# BT-USB.net
KiCad netlist of a schematic drawn in EAGLE
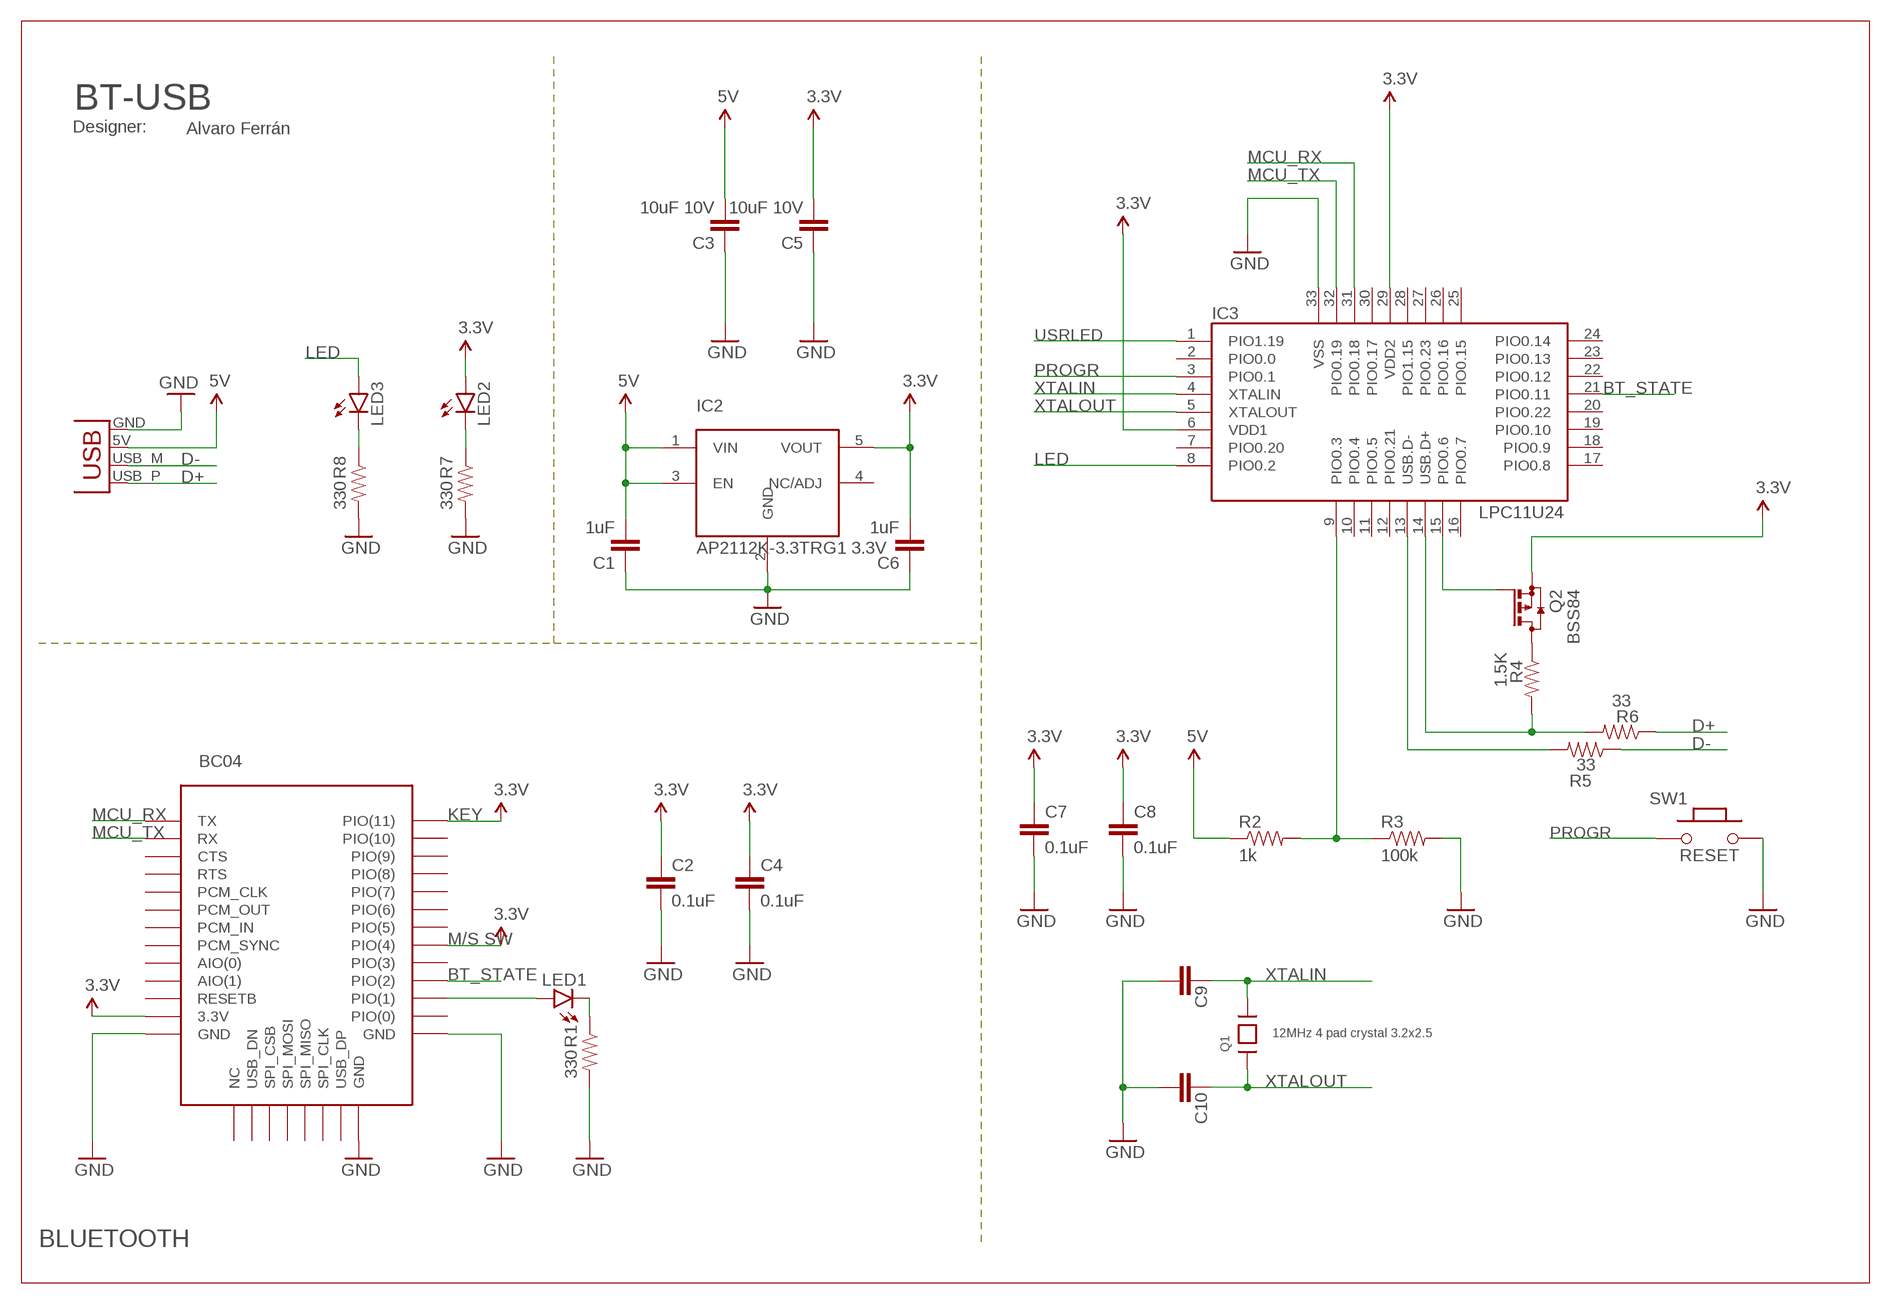
[diagram p0: schematic, sheet 1]

(export (version "E")
  (design (tool "Eeschema 10.0.6"))
  (components
    (comp (ref "C1")
      (value "1uF")
      (footprint "eagle-import:0402-CAP")
      (libsource (lib "eagle-import") (part "CAP0402-CAP"))
    )
    (comp (ref "C2")
      (value "0.1uF")
      (footprint "eagle-import:0402-CAP")
      (libsource (lib "eagle-import") (part "CAP0402-CAP"))
    )
    (comp (ref "C3")
      (value "10uF 10V")
      (footprint "eagle-import:0402-CAP")
      (libsource (lib "eagle-import") (part "CAP0402-CAP"))
    )
    (comp (ref "C4")
      (value "0.1uF")
      (footprint "eagle-import:0402-CAP")
      (libsource (lib "eagle-import") (part "CAP0402-CAP"))
    )
    (comp (ref "C5")
      (value "10uF 10V")
      (footprint "eagle-import:0402-CAP")
      (libsource (lib "eagle-import") (part "CAP0402-CAP"))
    )
    (comp (ref "C6")
      (value "1uF")
      (footprint "eagle-import:0402-CAP")
      (libsource (lib "eagle-import") (part "CAP0402-CAP"))
    )
    (comp (ref "C7")
      (value "0.1uF")
      (footprint "eagle-import:0402-CAP")
      (libsource (lib "eagle-import") (part "CAP0402-CAP"))
    )
    (comp (ref "C8")
      (value "0.1uF")
      (footprint "eagle-import:0402-CAP")
      (libsource (lib "eagle-import") (part "CAP0402-CAP"))
    )
    (comp (ref "C9")
      (value "27pF")
      (footprint "eagle-import:0402-CAP")
      (libsource (lib "eagle-import") (part "CAP0402-CAP"))
    )
    (comp (ref "C10")
      (value "27pF")
      (footprint "eagle-import:0402-CAP")
      (libsource (lib "eagle-import") (part "CAP0402-CAP"))
    )
    (comp (ref "IC1")
      (value "BC04_BLUETOOTH")
      (footprint "eagle-import:BC04")
      (libsource (lib "eagle-import") (part "BC04_BLUETOOTH"))
    )
    (comp (ref "IC2")
      (value "AP2112K-3.3TRG1 3.3V")
      (footprint "eagle-import:SOT23-5")
      (libsource (lib "eagle-import") (part "5PIN_REG"))
    )
    (comp (ref "IC3")
      (value "LPC11U24")
      (footprint "eagle-import:HVQFN33_5X5MM")
      (libsource (lib "eagle-import") (part "LPC11U2X_HVQFN33(5X5)"))
    )
    (comp (ref "J1")
      (value "USBPCB")
      (footprint "eagle-import:USB-A-PCB")
      (libsource (lib "eagle-import") (part "USBPCB"))
    )
    (comp (ref "LED1")
      (value "LED0603")
      (footprint "eagle-import:LED-0603")
      (libsource (lib "eagle-import") (part "LED0603"))
    )
    (comp (ref "LED2")
      (value "LED0603")
      (footprint "eagle-import:LED-0603")
      (libsource (lib "eagle-import") (part "LED0603"))
    )
    (comp (ref "LED3")
      (value "LED0603")
      (footprint "eagle-import:LED-0603")
      (libsource (lib "eagle-import") (part "LED0603"))
    )
    (comp (ref "Q1")
      (value "12MHz 4 pad crystal 3.2x2.5")
      (footprint "eagle-import:CRYSTAL_3.2X2.5")
      (libsource (lib "eagle-import") (part "CRYSTAL3.2X2.5"))
    )
    (comp (ref "Q2")
      (value "BSS84")
      (footprint "eagle-import:SOT23")
      (libsource (lib "eagle-import") (part "BSS84"))
    )
    (comp (ref "R1")
      (value "330")
      (footprint "eagle-import:0402-RES")
      (libsource (lib "eagle-import") (part "RESISTOR0402-RES"))
    )
    (comp (ref "R2")
      (value "1k")
      (footprint "eagle-import:0402-RES")
      (libsource (lib "eagle-import") (part "RESISTOR0402-RES"))
    )
    (comp (ref "R3")
      (value "100k")
      (footprint "eagle-import:0402-RES")
      (libsource (lib "eagle-import") (part "RESISTOR0402-RES"))
    )
    (comp (ref "R4")
      (value "1.5K")
      (footprint "eagle-import:0402-RES")
      (libsource (lib "eagle-import") (part "RESISTOR0402-RES"))
    )
    (comp (ref "R5")
      (value "33")
      (footprint "eagle-import:0402-RES")
      (libsource (lib "eagle-import") (part "RESISTOR0402-RES"))
    )
    (comp (ref "R6")
      (value "33")
      (footprint "eagle-import:0402-RES")
      (libsource (lib "eagle-import") (part "RESISTOR0402-RES"))
    )
    (comp (ref "R7")
      (value "330")
      (footprint "eagle-import:0402-RES")
      (libsource (lib "eagle-import") (part "RESISTOR0402-RES"))
    )
    (comp (ref "R8")
      (value "330")
      (footprint "eagle-import:0402-RES")
      (libsource (lib "eagle-import") (part "RESISTOR0402-RES"))
    )
    (comp (ref "SW1")
      (value "RESET")
      (footprint "eagle-import:157SW")
      (libsource (lib "eagle-import") (part "PB157"))
    )
  )
  (nets
    (net (code "1") (name "/BT_STATE") (class "Default")
      (node (ref "IC1") (pin "P$25") (pinfunction "PIO(2)_P$25") (pintype "bidirectional"))
      (node (ref "IC3") (pin "21") (pinfunction "PIO0.11_21") (pintype "bidirectional"))
    )
    (net (code "2") (name "/D+") (class "Default")
      (node (ref "J1") (pin "USB_P") (pinfunction "D+_USB_P") (pintype "bidirectional"))
      (node (ref "R6") (pin "1") (pinfunction "1_1") (pintype "passive"))
    )
    (net (code "3") (name "/D-") (class "Default")
      (node (ref "J1") (pin "USB_M") (pinfunction "D-_USB_M") (pintype "bidirectional"))
      (node (ref "R5") (pin "1") (pinfunction "1_1") (pintype "passive"))
    )
    (net (code "4") (name "/LED") (class "Default")
      (node (ref "IC3") (pin "8") (pinfunction "PIO0.2_8") (pintype "bidirectional"))
      (node (ref "LED3") (pin "A") (pinfunction "A_A") (pintype "passive"))
    )
    (net (code "5") (name "/MCU_RX") (class "Default")
      (node (ref "IC1") (pin "P$1") (pinfunction "TX_P$1") (pintype "bidirectional"))
      (node (ref "IC3") (pin "31") (pinfunction "PIO0.18_31") (pintype "bidirectional"))
    )
    (net (code "6") (name "/MCU_TX") (class "Default")
      (node (ref "IC1") (pin "P$2") (pinfunction "RX_P$2") (pintype "bidirectional"))
      (node (ref "IC3") (pin "32") (pinfunction "PIO0.19_32") (pintype "bidirectional"))
    )
    (net (code "7") (name "/PROGR") (class "Default")
      (node (ref "IC3") (pin "3") (pinfunction "PIO0.1_3") (pintype "bidirectional"))
      (node (ref "SW1") (pin "1") (pinfunction "1_1") (pintype "passive"))
    )
    (net (code "8") (name "/USRLED") (class "Default")
      (node (ref "IC3") (pin "1") (pinfunction "PIO1.19_1") (pintype "bidirectional"))
    )
    (net (code "9") (name "/XTALIN") (class "Default")
      (node (ref "C9") (pin "1") (pinfunction "1_1") (pintype "passive"))
      (node (ref "IC3") (pin "4") (pinfunction "XTALIN_4") (pintype "bidirectional"))
      (node (ref "Q1") (pin "3") (pinfunction "P$2_3") (pintype "passive"))
    )
    (net (code "10") (name "/XTALOUT") (class "Default")
      (node (ref "C10") (pin "1") (pinfunction "1_1") (pintype "passive"))
      (node (ref "IC3") (pin "5") (pinfunction "XTALOUT_5") (pintype "bidirectional"))
      (node (ref "Q1") (pin "1") (pinfunction "P$1_1") (pintype "passive"))
    )
    (net (code "11") (name "3.3V") (class "Default")
      (node (ref "C2") (pin "1") (pinfunction "1_1") (pintype "passive"))
      (node (ref "C4") (pin "1") (pinfunction "1_1") (pintype "passive"))
      (node (ref "C5") (pin "2") (pinfunction "2_2") (pintype "passive"))
      (node (ref "C6") (pin "2") (pinfunction "2_2") (pintype "passive"))
      (node (ref "C7") (pin "1") (pinfunction "1_1") (pintype "passive"))
      (node (ref "C8") (pin "1") (pinfunction "1_1") (pintype "passive"))
      (node (ref "IC1") (pin "P$12") (pinfunction "3.3V_P$12") (pintype "bidirectional"))
      (node (ref "IC1") (pin "P$27") (pinfunction "PIO(4)_P$27") (pintype "bidirectional"))
      (node (ref "IC1") (pin "P$34") (pinfunction "PIO(11)_P$34") (pintype "bidirectional"))
      (node (ref "IC2") (pin "5") (pinfunction "VOUT_5") (pintype "bidirectional"))
      (node (ref "IC3") (pin "29") (pinfunction "VDD2_29") (pintype "bidirectional"))
      (node (ref "IC3") (pin "6") (pinfunction "VDD1_6") (pintype "bidirectional"))
      (node (ref "LED2") (pin "A") (pinfunction "A_A") (pintype "passive"))
      (node (ref "Q2") (pin "2") (pinfunction "S_2") (pintype "passive"))
    )
    (net (code "12") (name "5V") (class "Default")
      (node (ref "C1") (pin "2") (pinfunction "2_2") (pintype "passive"))
      (node (ref "C3") (pin "2") (pinfunction "2_2") (pintype "passive"))
      (node (ref "IC2") (pin "1") (pinfunction "VIN_1") (pintype "bidirectional"))
      (node (ref "IC2") (pin "3") (pinfunction "EN_3") (pintype "bidirectional"))
      (node (ref "J1") (pin "5V") (pinfunction "VBUS_5V") (pintype "bidirectional"))
      (node (ref "R2") (pin "1") (pinfunction "1_1") (pintype "passive"))
    )
    (net (code "13") (name "GND") (class "Default")
      (node (ref "C1") (pin "1") (pinfunction "1_1") (pintype "passive"))
      (node (ref "C10") (pin "2") (pinfunction "2_2") (pintype "passive"))
      (node (ref "C2") (pin "2") (pinfunction "2_2") (pintype "passive"))
      (node (ref "C3") (pin "1") (pinfunction "1_1") (pintype "passive"))
      (node (ref "C4") (pin "2") (pinfunction "2_2") (pintype "passive"))
      (node (ref "C5") (pin "1") (pinfunction "1_1") (pintype "passive"))
      (node (ref "C6") (pin "1") (pinfunction "1_1") (pintype "passive"))
      (node (ref "C7") (pin "2") (pinfunction "2_2") (pintype "passive"))
      (node (ref "C8") (pin "2") (pinfunction "2_2") (pintype "passive"))
      (node (ref "C9") (pin "2") (pinfunction "2_2") (pintype "passive"))
      (node (ref "IC1") (pin "P$13") (pinfunction "GND_P$13") (pintype "bidirectional"))
      (node (ref "IC1") (pin "P$21") (pinfunction "GND_P$21") (pintype "bidirectional"))
      (node (ref "IC1") (pin "P$22") (pinfunction "GND_P$22") (pintype "bidirectional"))
      (node (ref "IC2") (pin "2") (pinfunction "GND_2") (pintype "bidirectional"))
      (node (ref "IC3") (pin "33") (pinfunction "VSS_33") (pintype "bidirectional"))
      (node (ref "J1") (pin "GND") (pinfunction "GND_GND") (pintype "bidirectional"))
      (node (ref "R1") (pin "2") (pinfunction "2_2") (pintype "passive"))
      (node (ref "R3") (pin "2") (pinfunction "2_2") (pintype "passive"))
      (node (ref "R7") (pin "2") (pinfunction "2_2") (pintype "passive"))
      (node (ref "R8") (pin "2") (pinfunction "2_2") (pintype "passive"))
      (node (ref "SW1") (pin "2") (pinfunction "2_2") (pintype "passive"))
    )
    (net (code "14") (name "Net-(IC1-PIO(1))") (class "Default")
      (node (ref "IC1") (pin "P$24") (pinfunction "PIO(1)_P$24") (pintype "bidirectional"))
      (node (ref "LED1") (pin "A") (pinfunction "A_A") (pintype "passive"))
    )
    (net (code "15") (name "Net-(IC3-PIO0.3)") (class "Default")
      (node (ref "IC3") (pin "9") (pinfunction "PIO0.3_9") (pintype "bidirectional"))
      (node (ref "R2") (pin "2") (pinfunction "2_2") (pintype "passive"))
      (node (ref "R3") (pin "1") (pinfunction "1_1") (pintype "passive"))
    )
    (net (code "16") (name "Net-(IC3-PIO0.6)") (class "Default")
      (node (ref "IC3") (pin "15") (pinfunction "PIO0.6_15") (pintype "bidirectional"))
      (node (ref "Q2") (pin "1") (pinfunction "G_1") (pintype "passive"))
    )
    (net (code "17") (name "Net-(IC3-USB.D+)") (class "Default")
      (node (ref "IC3") (pin "14") (pinfunction "USB.D+_14") (pintype "bidirectional"))
      (node (ref "R4") (pin "2") (pinfunction "2_2") (pintype "passive"))
      (node (ref "R6") (pin "2") (pinfunction "2_2") (pintype "passive"))
    )
    (net (code "18") (name "Net-(IC3-USB.D-)") (class "Default")
      (node (ref "IC3") (pin "13") (pinfunction "USB.D-_13") (pintype "bidirectional"))
      (node (ref "R5") (pin "2") (pinfunction "2_2") (pintype "passive"))
    )
    (net (code "19") (name "Net-(LED1-PadC)") (class "Default")
      (node (ref "LED1") (pin "C") (pinfunction "C_C") (pintype "passive"))
      (node (ref "R1") (pin "1") (pinfunction "1_1") (pintype "passive"))
    )
    (net (code "20") (name "Net-(LED2-PadC)") (class "Default")
      (node (ref "LED2") (pin "C") (pinfunction "C_C") (pintype "passive"))
      (node (ref "R7") (pin "1") (pinfunction "1_1") (pintype "passive"))
    )
    (net (code "21") (name "Net-(LED3-PadC)") (class "Default")
      (node (ref "LED3") (pin "C") (pinfunction "C_C") (pintype "passive"))
      (node (ref "R8") (pin "1") (pinfunction "1_1") (pintype "passive"))
    )
    (net (code "22") (name "Net-(Q2-D)") (class "Default")
      (node (ref "Q2") (pin "3") (pinfunction "D_3") (pintype "passive"))
      (node (ref "R4") (pin "1") (pinfunction "1_1") (pintype "passive"))
    )
    (net (code "23") (name "unconnected-(IC1-AIO(0)-PadP$9)") (class "Default")
      (node (ref "IC1") (pin "P$9") (pinfunction "AIO(0)_P$9") (pintype "bidirectional"))
    )
    (net (code "24") (name "unconnected-(IC1-AIO(1)-PadP$10)") (class "Default")
      (node (ref "IC1") (pin "P$10") (pinfunction "AIO(1)_P$10") (pintype "bidirectional"))
    )
    (net (code "25") (name "unconnected-(IC1-CTS-PadP$3)") (class "Default")
      (node (ref "IC1") (pin "P$3") (pinfunction "CTS_P$3") (pintype "bidirectional"))
    )
    (net (code "26") (name "unconnected-(IC1-NC-PadP$14)") (class "Default")
      (node (ref "IC1") (pin "P$14") (pinfunction "NC_P$14") (pintype "bidirectional"))
    )
    (net (code "27") (name "unconnected-(IC1-PCM_CLK-PadP$5)") (class "Default")
      (node (ref "IC1") (pin "P$5") (pinfunction "PCM_CLK_P$5") (pintype "bidirectional"))
    )
    (net (code "28") (name "unconnected-(IC1-PCM_IN-PadP$7)") (class "Default")
      (node (ref "IC1") (pin "P$7") (pinfunction "PCM_IN_P$7") (pintype "bidirectional"))
    )
    (net (code "29") (name "unconnected-(IC1-PCM_OUT-PadP$6)") (class "Default")
      (node (ref "IC1") (pin "P$6") (pinfunction "PCM_OUT_P$6") (pintype "bidirectional"))
    )
    (net (code "30") (name "unconnected-(IC1-PCM_SYNC-PadP$8)") (class "Default")
      (node (ref "IC1") (pin "P$8") (pinfunction "PCM_SYNC_P$8") (pintype "bidirectional"))
    )
    (net (code "31") (name "unconnected-(IC1-PIO(0)-PadP$23)") (class "Default")
      (node (ref "IC1") (pin "P$23") (pinfunction "PIO(0)_P$23") (pintype "bidirectional"))
    )
    (net (code "32") (name "unconnected-(IC1-PIO(3)-PadP$26)") (class "Default")
      (node (ref "IC1") (pin "P$26") (pinfunction "PIO(3)_P$26") (pintype "bidirectional"))
    )
    (net (code "33") (name "unconnected-(IC1-PIO(5)-PadP$28)") (class "Default")
      (node (ref "IC1") (pin "P$28") (pinfunction "PIO(5)_P$28") (pintype "bidirectional"))
    )
    (net (code "34") (name "unconnected-(IC1-PIO(6)-PadP$29)") (class "Default")
      (node (ref "IC1") (pin "P$29") (pinfunction "PIO(6)_P$29") (pintype "bidirectional"))
    )
    (net (code "35") (name "unconnected-(IC1-PIO(7)-PadP$30)") (class "Default")
      (node (ref "IC1") (pin "P$30") (pinfunction "PIO(7)_P$30") (pintype "bidirectional"))
    )
    (net (code "36") (name "unconnected-(IC1-PIO(8)-PadP$31)") (class "Default")
      (node (ref "IC1") (pin "P$31") (pinfunction "PIO(8)_P$31") (pintype "bidirectional"))
    )
    (net (code "37") (name "unconnected-(IC1-PIO(9)-PadP$32)") (class "Default")
      (node (ref "IC1") (pin "P$32") (pinfunction "PIO(9)_P$32") (pintype "bidirectional"))
    )
    (net (code "38") (name "unconnected-(IC1-PIO(10)-PadP$33)") (class "Default")
      (node (ref "IC1") (pin "P$33") (pinfunction "PIO(10)_P$33") (pintype "bidirectional"))
    )
    (net (code "39") (name "unconnected-(IC1-RESETB-PadP$11)") (class "Default")
      (node (ref "IC1") (pin "P$11") (pinfunction "RESETB_P$11") (pintype "bidirectional"))
    )
    (net (code "40") (name "unconnected-(IC1-RTS-PadP$4)") (class "Default")
      (node (ref "IC1") (pin "P$4") (pinfunction "RTS_P$4") (pintype "bidirectional"))
    )
    (net (code "41") (name "unconnected-(IC1-SPI_CLK-PadP$19)") (class "Default")
      (node (ref "IC1") (pin "P$19") (pinfunction "SPI_CLK_P$19") (pintype "bidirectional"))
    )
    (net (code "42") (name "unconnected-(IC1-SPI_CSB-PadP$16)") (class "Default")
      (node (ref "IC1") (pin "P$16") (pinfunction "SPI_CSB_P$16") (pintype "bidirectional"))
    )
    (net (code "43") (name "unconnected-(IC1-SPI_MISO-PadP$18)") (class "Default")
      (node (ref "IC1") (pin "P$18") (pinfunction "SPI_MISO_P$18") (pintype "bidirectional"))
    )
    (net (code "44") (name "unconnected-(IC1-SPI_MOSI-PadP$17)") (class "Default")
      (node (ref "IC1") (pin "P$17") (pinfunction "SPI_MOSI_P$17") (pintype "bidirectional"))
    )
    (net (code "45") (name "unconnected-(IC1-USB_DN-PadP$15)") (class "Default")
      (node (ref "IC1") (pin "P$15") (pinfunction "USB_DN_P$15") (pintype "bidirectional"))
    )
    (net (code "46") (name "unconnected-(IC1-USB_DP-PadP$20)") (class "Default")
      (node (ref "IC1") (pin "P$20") (pinfunction "USB_DP_P$20") (pintype "bidirectional"))
    )
    (net (code "47") (name "unconnected-(IC2-NC{slash}ADJ-Pad4)") (class "Default")
      (node (ref "IC2") (pin "4") (pinfunction "NC/ADJ_4") (pintype "bidirectional"))
    )
    (net (code "48") (name "unconnected-(IC3-PIO0.0-Pad2)") (class "Default")
      (node (ref "IC3") (pin "2") (pinfunction "PIO0.0_2") (pintype "bidirectional"))
    )
    (net (code "49") (name "unconnected-(IC3-PIO0.4-Pad10)") (class "Default")
      (node (ref "IC3") (pin "10") (pinfunction "PIO0.4_10") (pintype "bidirectional"))
    )
    (net (code "50") (name "unconnected-(IC3-PIO0.5-Pad11)") (class "Default")
      (node (ref "IC3") (pin "11") (pinfunction "PIO0.5_11") (pintype "bidirectional"))
    )
    (net (code "51") (name "unconnected-(IC3-PIO0.7-Pad16)") (class "Default")
      (node (ref "IC3") (pin "16") (pinfunction "PIO0.7_16") (pintype "bidirectional"))
    )
    (net (code "52") (name "unconnected-(IC3-PIO0.8-Pad17)") (class "Default")
      (node (ref "IC3") (pin "17") (pinfunction "PIO0.8_17") (pintype "bidirectional"))
    )
    (net (code "53") (name "unconnected-(IC3-PIO0.9-Pad18)") (class "Default")
      (node (ref "IC3") (pin "18") (pinfunction "PIO0.9_18") (pintype "bidirectional"))
    )
    (net (code "54") (name "unconnected-(IC3-PIO0.10-Pad19)") (class "Default")
      (node (ref "IC3") (pin "19") (pinfunction "PIO0.10_19") (pintype "bidirectional"))
    )
    (net (code "55") (name "unconnected-(IC3-PIO0.12-Pad22)") (class "Default")
      (node (ref "IC3") (pin "22") (pinfunction "PIO0.12_22") (pintype "bidirectional"))
    )
    (net (code "56") (name "unconnected-(IC3-PIO0.13-Pad23)") (class "Default")
      (node (ref "IC3") (pin "23") (pinfunction "PIO0.13_23") (pintype "bidirectional"))
    )
    (net (code "57") (name "unconnected-(IC3-PIO0.14-Pad24)") (class "Default")
      (node (ref "IC3") (pin "24") (pinfunction "PIO0.14_24") (pintype "bidirectional"))
    )
    (net (code "58") (name "unconnected-(IC3-PIO0.15-Pad25)") (class "Default")
      (node (ref "IC3") (pin "25") (pinfunction "PIO0.15_25") (pintype "bidirectional"))
    )
    (net (code "59") (name "unconnected-(IC3-PIO0.16-Pad26)") (class "Default")
      (node (ref "IC3") (pin "26") (pinfunction "PIO0.16_26") (pintype "bidirectional"))
    )
    (net (code "60") (name "unconnected-(IC3-PIO0.17-Pad30)") (class "Default")
      (node (ref "IC3") (pin "30") (pinfunction "PIO0.17_30") (pintype "bidirectional"))
    )
    (net (code "61") (name "unconnected-(IC3-PIO0.20-Pad7)") (class "Default")
      (node (ref "IC3") (pin "7") (pinfunction "PIO0.20_7") (pintype "bidirectional"))
    )
    (net (code "62") (name "unconnected-(IC3-PIO0.21-Pad12)") (class "Default")
      (node (ref "IC3") (pin "12") (pinfunction "PIO0.21_12") (pintype "bidirectional"))
    )
    (net (code "63") (name "unconnected-(IC3-PIO0.22-Pad20)") (class "Default")
      (node (ref "IC3") (pin "20") (pinfunction "PIO0.22_20") (pintype "bidirectional"))
    )
    (net (code "64") (name "unconnected-(IC3-PIO0.23-Pad27)") (class "Default")
      (node (ref "IC3") (pin "27") (pinfunction "PIO0.23_27") (pintype "bidirectional"))
    )
    (net (code "65") (name "unconnected-(IC3-PIO1.15-Pad28)") (class "Default")
      (node (ref "IC3") (pin "28") (pinfunction "PIO1.15_28") (pintype "bidirectional"))
    )
  )
)
